# ProPrj___2025-12-14-15-56-23.net
KiCad netlist of a schematic drawn in EasyEDA Pro
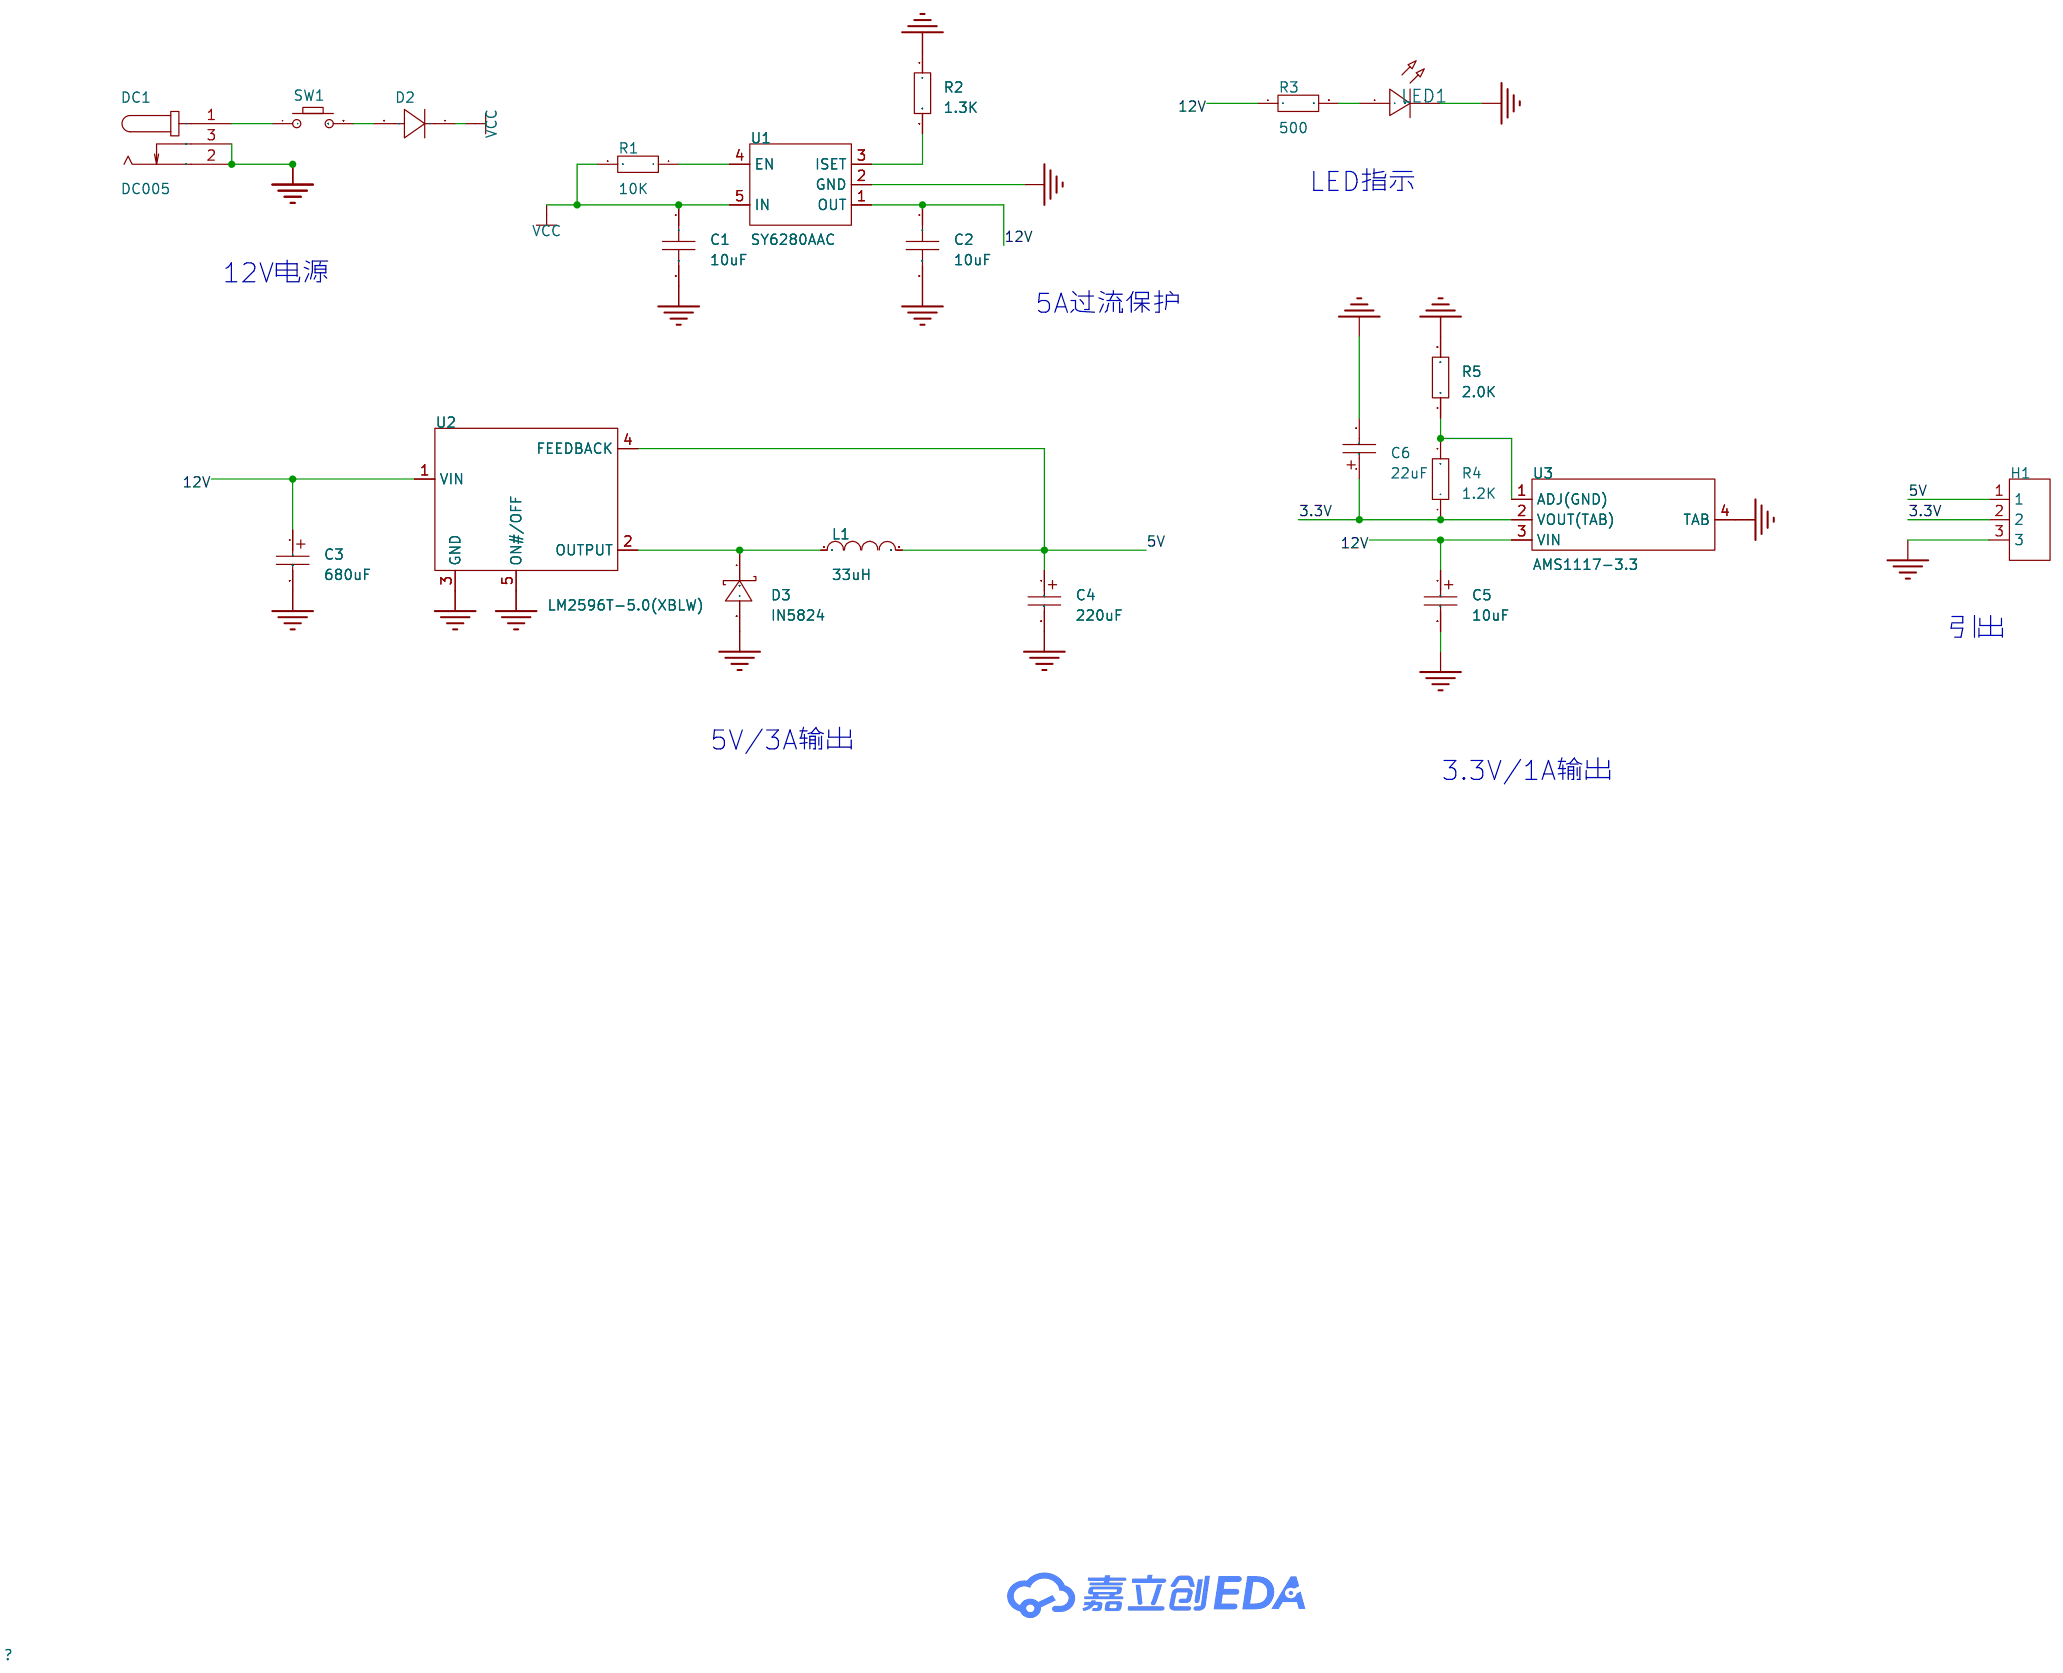
[diagram p0: schematic sheet]

(export (version "E")
  (design (tool "Eeschema 10.0.6"))
  (components
    (comp (ref "C1")
      (value "10uF")
      (footprint "easyedapro:C0603")
      (libsource (lib "easyedapro") (part "Capacitance"))
    )
    (comp (ref "C2")
      (value "10uF")
      (footprint "easyedapro:C0603")
      (libsource (lib "easyedapro") (part "Capacitance"))
    )
    (comp (ref "C3")
      (value "680uF")
      (footprint "easyedapro:C_Ele_SMD_3x5.4mm")
      (libsource (lib "easyedapro") (part "CAP"))
    )
    (comp (ref "C4")
      (value "220uF")
      (footprint "easyedapro:C_Ele_SMD_3x5.4mm")
      (libsource (lib "easyedapro") (part "CAP"))
    )
    (comp (ref "C5")
      (value "10uF")
      (footprint "easyedapro:C_Ele_SMD_3x5.4mm")
      (libsource (lib "easyedapro") (part "CAP"))
    )
    (comp (ref "C6")
      (value "22uF")
      (footprint "easyedapro:C_Ele_SMD_3x5.4mm")
      (libsource (lib "easyedapro") (part "CAP"))
    )
    (comp (ref "D2")
      (value "~")
      (footprint "easyedapro:DO_1N4007")
      (libsource (lib "easyedapro") (part "D_1N4007"))
    )
    (comp (ref "D3")
      (value "IN5824")
      (footprint "easyedapro:SMAF_L3.5-W2.6-LS4.7-RD")
      (libsource (lib "easyedapro") (part "IN5824"))
    )
    (comp (ref "DC1")
      (value "DC005")
      (footprint "easyedapro:DC-IN-TH_DC005")
      (description "连接器类型:DC电源插座;安装方式:弯插;触点内径:2mm;触点外径:6.3mm;额定电流:500mA;额定电压:12V;工作温度:-30°C~+70°C;")
      (fields (field (name "Manufacturer") "SHOU HAN(首韩)"))
      (libsource (lib "easyedapro") (part "DC005_C431533"))
    )
    (comp (ref "H1")
      (value "~")
      (footprint "easyedapro:HDR-TH_3P-P2.54-V-F")
      (libsource (lib "easyedapro") (part "PM254V-11-03-H85"))
    )
    (comp (ref "L1")
      (value "33uH")
      (footprint "easyedapro:L0603")
      (libsource (lib "easyedapro") (part "SDFL1608S100KTF"))
    )
    (comp (ref "LED1")
      (value "~")
      (footprint "easyedapro:LED_0603")
      (libsource (lib "easyedapro") (part "LED_R"))
    )
    (comp (ref "R1") (value "10K") (footprint "easyedapro:R0603") (libsource (lib "easyedapro") (part "电阻")))
    (comp (ref "R2") (value "1.3K") (footprint "easyedapro:R0603") (libsource (lib "easyedapro") (part "电阻")))
    (comp (ref "R3") (value "500") (footprint "easyedapro:R0603") (libsource (lib "easyedapro") (part "电阻")))
    (comp (ref "R4") (value "1.2K") (footprint "easyedapro:R0603") (libsource (lib "easyedapro") (part "电阻")))
    (comp (ref "R5") (value "2.0K") (footprint "easyedapro:R0603") (libsource (lib "easyedapro") (part "电阻")))
    (comp (ref "SW1")
      (value "~")
      (footprint "easyedapro:Key_TH_3.5x6x4.3")
      (libsource (lib "easyedapro") (part "Key_TH_3.5x6x4.3"))
    )
    (comp (ref "U1")
      (value "SY6280AAC")
      (footprint "easyedapro:SOT-23-5_L3.0-W1.7-P0.95-LS2.8-BR")
      (libsource (lib "easyedapro") (part "SY6280AAC_C9900003867"))
    )
    (comp (ref "U2")
      (value "LM2596T-5.0(XBLW)")
      (footprint "easyedapro:TO-220-5L_L10.2-W4.5-P1.71-L")
      (description "功能类型:降压型;工作电压:6V~40V;输出电压:5V;输出电流:3A;输出类型:固定;")
      (fields (field (name "Manufacturer") "XBLW(芯伯乐)"))
      (libsource (lib "easyedapro") (part "LM2596T-5.0(XBLW)"))
    )
    (comp (ref "U3")
      (value "AMS1117-3.3")
      (footprint "easyedapro:SOT-223-4_L6.5-W3.5-P2.30-LS7.0-BR")
      (description "输出类型:固定;工作电压:12V;输出电压:3.3V;输出电流:1A;电源纹波抑制比(PSRR):60dB@(120Hz);输出极性:正极;")
      (fields (field (name "Manufacturer") "UMW(友台半导体)"))
      (libsource (lib "easyedapro") (part "AMS1117-3.3_C347222"))
    )
  )
  (nets
    (net (code "1") (name "/3.3V") (class "Default")
      (node (ref "C6") (pin "1") (pinfunction "1_1") (pintype "input"))
      (node (ref "H1") (pin "2") (pinfunction "2_2") (pintype "unspecified"))
      (node (ref "R4") (pin "1") (pinfunction "1_1") (pintype "input"))
      (node (ref "U3") (pin "2") (pinfunction "VOUT(TAB)_2") (pintype "unspecified"))
    )
    (net (code "2") (name "/5V") (class "Default")
      (node (ref "C4") (pin "1") (pinfunction "1_1") (pintype "input"))
      (node (ref "H1") (pin "1") (pinfunction "1_1") (pintype "unspecified"))
      (node (ref "L1") (pin "2") (pinfunction "2_2") (pintype "unspecified"))
      (node (ref "U2") (pin "4") (pinfunction "FEEDBACK_4") (pintype "unspecified"))
    )
    (net (code "3") (name "/12V") (class "Default")
      (node (ref "C2") (pin "1") (pinfunction "1_1") (pintype "input"))
      (node (ref "C3") (pin "1") (pinfunction "1_1") (pintype "input"))
      (node (ref "C5") (pin "1") (pinfunction "1_1") (pintype "input"))
      (node (ref "R3") (pin "1") (pinfunction "1_1") (pintype "input"))
      (node (ref "U1") (pin "1") (pinfunction "OUT_1") (pintype "unspecified"))
      (node (ref "U2") (pin "1") (pinfunction "VIN_1") (pintype "unspecified"))
      (node (ref "U3") (pin "3") (pinfunction "VIN_3") (pintype "unspecified"))
    )
    (net (code "4") (name "GND") (class "Default")
      (node (ref "C1") (pin "2") (pinfunction "2_2") (pintype "input"))
      (node (ref "C2") (pin "2") (pinfunction "2_2") (pintype "input"))
      (node (ref "C3") (pin "2") (pinfunction "2_2") (pintype "input"))
      (node (ref "C4") (pin "2") (pinfunction "2_2") (pintype "input"))
      (node (ref "C5") (pin "2") (pinfunction "2_2") (pintype "input"))
      (node (ref "C6") (pin "2") (pinfunction "2_2") (pintype "input"))
      (node (ref "D3") (pin "2") (pinfunction "A_2") (pintype "unspecified"))
      (node (ref "DC1") (pin "2") (pinfunction "2_2") (pintype "unspecified"))
      (node (ref "DC1") (pin "3") (pinfunction "3_3") (pintype "unspecified"))
      (node (ref "H1") (pin "3") (pinfunction "3_3") (pintype "unspecified"))
      (node (ref "LED1") (pin "1") (pinfunction "C_1") (pintype "input"))
      (node (ref "R2") (pin "1") (pinfunction "1_1") (pintype "input"))
      (node (ref "R5") (pin "2") (pinfunction "2_2") (pintype "input"))
      (node (ref "U1") (pin "2") (pinfunction "GND_2") (pintype "unspecified"))
      (node (ref "U2") (pin "3") (pinfunction "GND_3") (pintype "unspecified"))
      (node (ref "U2") (pin "5") (pinfunction "ON#/OFF_5") (pintype "unspecified"))
      (node (ref "U3") (pin "4") (pinfunction "TAB_4") (pintype "unspecified"))
    )
    (net (code "5") (name "Net-(D2-A)") (class "Default")
      (node (ref "D2") (pin "2") (pinfunction "A_2") (pintype "input"))
      (node (ref "SW1") (pin "B") (pinfunction "B_B") (pintype "input"))
    )
    (net (code "6") (name "Net-(D3-C)") (class "Default")
      (node (ref "D3") (pin "1") (pinfunction "C_1") (pintype "unspecified"))
      (node (ref "L1") (pin "1") (pinfunction "1_1") (pintype "unspecified"))
      (node (ref "U2") (pin "2") (pinfunction "OUTPUT_2") (pintype "unspecified"))
    )
    (net (code "7") (name "Net-(DC1-Pad1)") (class "Default")
      (node (ref "DC1") (pin "1") (pinfunction "1_1") (pintype "unspecified"))
      (node (ref "SW1") (pin "A") (pinfunction "A_A") (pintype "input"))
    )
    (net (code "8") (name "Net-(LED1-A)") (class "Default")
      (node (ref "LED1") (pin "2") (pinfunction "A_2") (pintype "input"))
      (node (ref "R3") (pin "2") (pinfunction "2_2") (pintype "input"))
    )
    (net (code "9") (name "Net-(U1-EN)") (class "Default")
      (node (ref "R1") (pin "1") (pinfunction "1_1") (pintype "input"))
      (node (ref "U1") (pin "4") (pinfunction "EN_4") (pintype "unspecified"))
    )
    (net (code "10") (name "Net-(U1-ISET)") (class "Default")
      (node (ref "R2") (pin "2") (pinfunction "2_2") (pintype "input"))
      (node (ref "U1") (pin "3") (pinfunction "ISET_3") (pintype "unspecified"))
    )
    (net (code "11") (name "Net-(U3-ADJ(GND))") (class "Default")
      (node (ref "R4") (pin "2") (pinfunction "2_2") (pintype "input"))
      (node (ref "R5") (pin "1") (pinfunction "1_1") (pintype "input"))
      (node (ref "U3") (pin "1") (pinfunction "ADJ(GND)_1") (pintype "unspecified"))
    )
    (net (code "12") (name "VCC") (class "Default")
      (node (ref "C1") (pin "1") (pinfunction "1_1") (pintype "input"))
      (node (ref "D2") (pin "1") (pinfunction "K_1") (pintype "input"))
      (node (ref "R1") (pin "2") (pinfunction "2_2") (pintype "input"))
      (node (ref "U1") (pin "5") (pinfunction "IN_5") (pintype "unspecified"))
    )
  )
)
